# WindRose_V01_0B.net
KiCad netlist of a schematic drawn in EAGLE
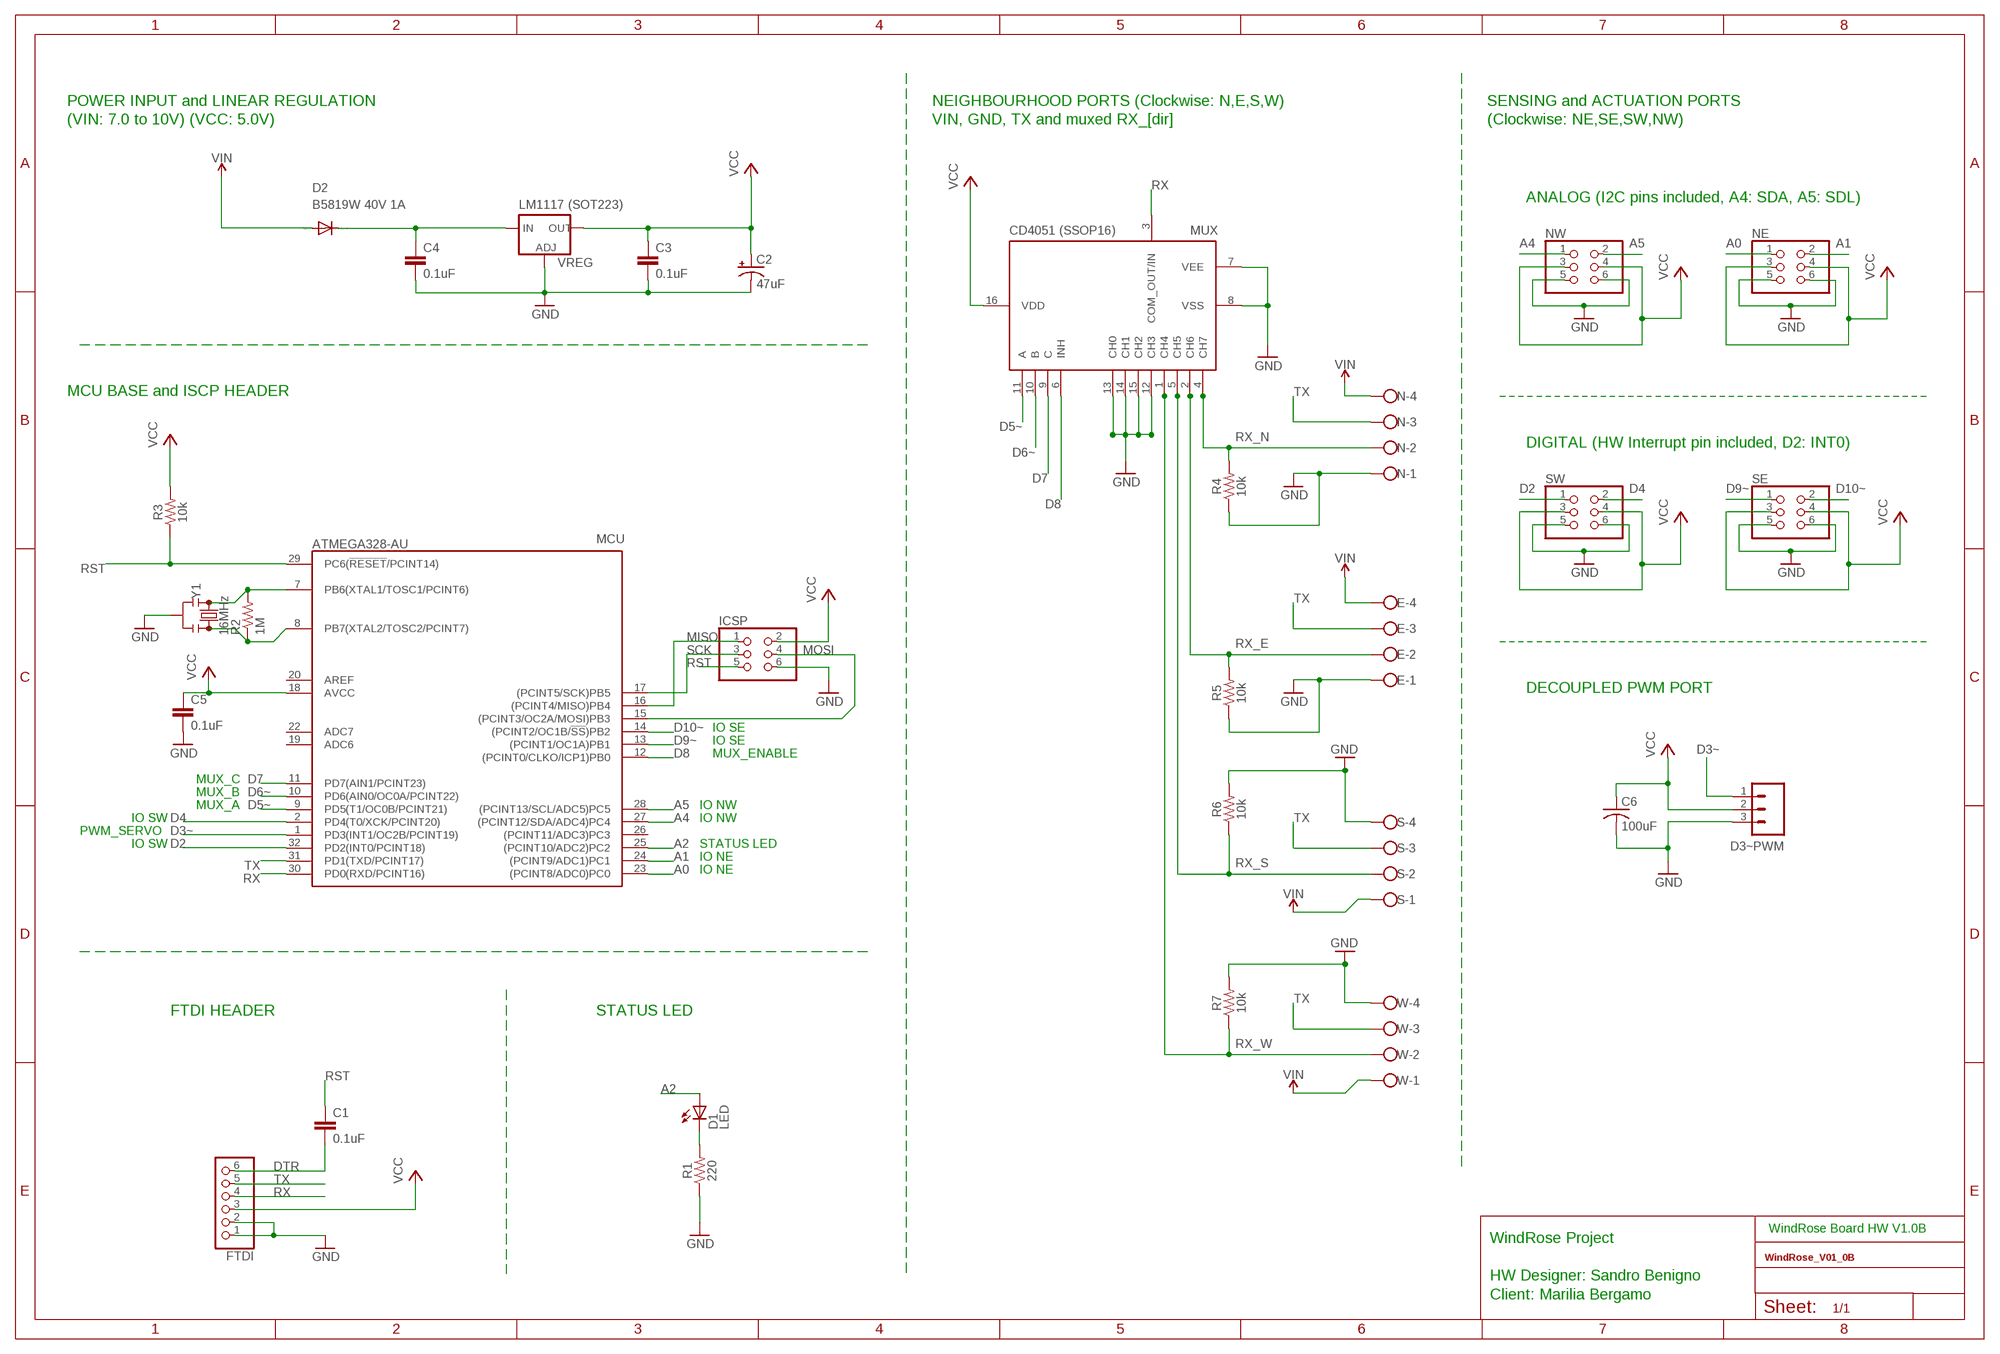
[diagram p0: schematic, sheet 1]

(export (version "E")
  (design (tool "Eeschema 10.0.6"))
  (components
    (comp (ref "C1")
      (value "0.1uF")
      (footprint "eagle-import:0402")
      (libsource (lib "eagle-import") (part "0.1UF-0402-6.3V-10%-X7R"))
    )
    (comp (ref "C2")
      (value "47uF")
      (footprint "eagle-import:EIA3216")
      (libsource (lib "eagle-import") (part "10UF-POLAR-EIA3216-16V-10%(TANT)"))
    )
    (comp (ref "C3")
      (value "0.1uF")
      (footprint "eagle-import:0402")
      (libsource (lib "eagle-import") (part "0.1UF-0402-6.3V-10%-X7R"))
    )
    (comp (ref "C4")
      (value "0.1uF")
      (footprint "eagle-import:0402")
      (libsource (lib "eagle-import") (part "0.1UF-0402-6.3V-10%-X7R"))
    )
    (comp (ref "C5")
      (value "0.1uF")
      (footprint "eagle-import:0402")
      (libsource (lib "eagle-import") (part "0.1UF-0402-6.3V-10%-X7R"))
    )
    (comp (ref "C6")
      (value "100uF")
      (footprint "eagle-import:C3216")
      (libsource (lib "eagle-import") (part "C-USC3216"))
    )
    (comp (ref "D1")
      (value "LED")
      (footprint "eagle-import:CHIP-LED0805")
      (libsource (lib "eagle-import") (part "LEDCHIP-LED0805"))
    )
    (comp (ref "D2")
      (value "B5819W 40V 1A")
      (footprint "eagle-import:SOD123")
      (libsource (lib "eagle-import") (part "DIODE-SOD123"))
    )
    (comp (ref "D3~PWM")
      (value "455-1750-1-ND")
      (footprint "eagle-import:1X03")
      (libsource (lib "eagle-import") (part "CONN_03"))
    )
    (comp (ref "E")
      (value "W237-4")
      (footprint "eagle-import:W237-4")
      (libsource (lib "eagle-import") (part "W237-4"))
    )
    (comp (ref "FTDI")
      (value "PINHD-1X6B")
      (footprint "eagle-import:1X06-BIG")
      (libsource (lib "eagle-import") (part "PINHD-1X6B"))
    )
    (comp (ref "ICSP")
      (value "PINHD-2X3")
      (footprint "eagle-import:2X03")
      (libsource (lib "eagle-import") (part "pinhead_PINHD-2X3"))
    )
    (comp (ref "MCU")
      (value "ATMEGA328-AU")
      (footprint "eagle-import:QFP32_7X7_0.80")
      (libsource (lib "eagle-import") (part "ATMEGA8-AU32"))
    )
    (comp (ref "MUX")
      (value "CD4051SSOP16")
      (footprint "eagle-import:SSOP16")
      (libsource (lib "eagle-import") (part "CD4051SSOP16"))
    )
    (comp (ref "N")
      (value "W237-4")
      (footprint "eagle-import:W237-4")
      (libsource (lib "eagle-import") (part "W237-4"))
    )
    (comp (ref "NE")
      (value "PINHD-2X3")
      (footprint "eagle-import:2X03")
      (libsource (lib "eagle-import") (part "PINHD-2X3"))
    )
    (comp (ref "NW")
      (value "PINHD-2X3")
      (footprint "eagle-import:2X03")
      (libsource (lib "eagle-import") (part "PINHD-2X3"))
    )
    (comp (ref "R1")
      (value "220")
      (footprint "eagle-import:0603")
      (libsource (lib "eagle-import") (part "220OHM-0603-1/10W-1%"))
    )
    (comp (ref "R2")
      (value "1M")
      (footprint "eagle-import:R0402")
      (libsource (lib "eagle-import") (part "R-US_R0402"))
    )
    (comp (ref "R3")
      (value "10k")
      (footprint "eagle-import:0402")
      (libsource (lib "eagle-import") (part "10KOHM-0402-1/16W-1%"))
    )
    (comp (ref "R4")
      (value "10k")
      (footprint "eagle-import:0402")
      (libsource (lib "eagle-import") (part "10KOHM-0402-1/16W-1%"))
    )
    (comp (ref "R5")
      (value "10k")
      (footprint "eagle-import:0402")
      (libsource (lib "eagle-import") (part "10KOHM-0402-1/16W-1%"))
    )
    (comp (ref "R6")
      (value "10k")
      (footprint "eagle-import:0402")
      (libsource (lib "eagle-import") (part "10KOHM-0402-1/16W-1%"))
    )
    (comp (ref "R7")
      (value "10k")
      (footprint "eagle-import:0402")
      (libsource (lib "eagle-import") (part "10KOHM-0402-1/16W-1%"))
    )
    (comp (ref "S")
      (value "W237-4")
      (footprint "eagle-import:W237-4")
      (libsource (lib "eagle-import") (part "W237-4"))
    )
    (comp (ref "SE")
      (value "PINHD-2X3")
      (footprint "eagle-import:2X03")
      (libsource (lib "eagle-import") (part "PINHD-2X3"))
    )
    (comp (ref "SW")
      (value "PINHD-2X3")
      (footprint "eagle-import:2X03")
      (libsource (lib "eagle-import") (part "PINHD-2X3"))
    )
    (comp (ref "VREG")
      (value "V_REG_LM1117SOT223")
      (footprint "eagle-import:SOT223")
      (libsource (lib "eagle-import") (part "V_REG_LM1117SOT223"))
    )
    (comp (ref "W")
      (value "W237-4")
      (footprint "eagle-import:W237-4")
      (libsource (lib "eagle-import") (part "W237-4"))
    )
    (comp (ref "Y1")
      (value "16MHz")
      (footprint "eagle-import:RESONATOR-SMD-3.2X1.3")
      (libsource (lib "eagle-import") (part "RESONATOR-16MHZSMD_3.2X1.3"))
    )
  )
  (nets
    (net (code "1") (name "/A0") (class "Default")
      (node (ref "MCU") (pin "23") (pinfunction "(PCINT8/ADC0)PC0_23") (pintype "bidirectional"))
      (node (ref "NE") (pin "1") (pinfunction "1_1") (pintype "passive"))
    )
    (net (code "2") (name "/A1") (class "Default")
      (node (ref "MCU") (pin "24") (pinfunction "(PCINT9/ADC1)PC1_24") (pintype "bidirectional"))
      (node (ref "NE") (pin "2") (pinfunction "2_2") (pintype "passive"))
    )
    (net (code "3") (name "/A2") (class "Default")
      (node (ref "D1") (pin "A") (pinfunction "A_A") (pintype "passive"))
      (node (ref "MCU") (pin "25") (pinfunction "(PCINT10/ADC2)PC2_25") (pintype "bidirectional"))
    )
    (net (code "4") (name "/A4") (class "Default")
      (node (ref "MCU") (pin "27") (pinfunction "(PCINT12/SDA/ADC4)PC4_27") (pintype "bidirectional"))
      (node (ref "NW") (pin "1") (pinfunction "1_1") (pintype "passive"))
    )
    (net (code "5") (name "/A5") (class "Default")
      (node (ref "MCU") (pin "28") (pinfunction "(PCINT13/SCL/ADC5)PC5_28") (pintype "bidirectional"))
      (node (ref "NW") (pin "2") (pinfunction "2_2") (pintype "passive"))
    )
    (net (code "6") (name "/D2") (class "Default")
      (node (ref "MCU") (pin "32") (pinfunction "PD2(INT0/PCINT18)_32") (pintype "bidirectional"))
      (node (ref "SW") (pin "1") (pinfunction "1_1") (pintype "passive"))
    )
    (net (code "7") (name "/D3~{}") (class "Default")
      (node (ref "D3~PWM") (pin "1") (pinfunction "1_1") (pintype "passive"))
      (node (ref "MCU") (pin "1") (pinfunction "PD3(INT1/OC2B/PCINT19)_1") (pintype "bidirectional"))
    )
    (net (code "8") (name "/D4") (class "Default")
      (node (ref "MCU") (pin "2") (pinfunction "PD4(T0/XCK/PCINT20)_2") (pintype "bidirectional"))
      (node (ref "SW") (pin "2") (pinfunction "2_2") (pintype "passive"))
    )
    (net (code "9") (name "/D5~{}") (class "Default")
      (node (ref "MCU") (pin "9") (pinfunction "PD5(T1/OC0B/PCINT21)_9") (pintype "bidirectional"))
      (node (ref "MUX") (pin "11") (pinfunction "A_11") (pintype "bidirectional"))
    )
    (net (code "10") (name "/D6~{}") (class "Default")
      (node (ref "MCU") (pin "10") (pinfunction "PD6(AIN0/OC0A/PCINT22)_10") (pintype "bidirectional"))
      (node (ref "MUX") (pin "10") (pinfunction "B_10") (pintype "bidirectional"))
    )
    (net (code "11") (name "/D7") (class "Default")
      (node (ref "MCU") (pin "11") (pinfunction "PD7(AIN1/PCINT23)_11") (pintype "bidirectional"))
      (node (ref "MUX") (pin "9") (pinfunction "C_9") (pintype "bidirectional"))
    )
    (net (code "12") (name "/D8") (class "Default")
      (node (ref "MCU") (pin "12") (pinfunction "(PCINT0/CLKO/ICP1)PB0_12") (pintype "bidirectional"))
      (node (ref "MUX") (pin "6") (pinfunction "INH_6") (pintype "bidirectional"))
    )
    (net (code "13") (name "/D9~{}") (class "Default")
      (node (ref "MCU") (pin "13") (pinfunction "(PCINT1/OC1A)PB1_13") (pintype "bidirectional"))
      (node (ref "SE") (pin "1") (pinfunction "1_1") (pintype "passive"))
    )
    (net (code "14") (name "/D10~{}") (class "Default")
      (node (ref "MCU") (pin "14") (pinfunction "(PCINT2/OC1B/~{SS})PB2_14") (pintype "bidirectional"))
      (node (ref "SE") (pin "2") (pinfunction "2_2") (pintype "passive"))
    )
    (net (code "15") (name "/DTR") (class "Default")
      (node (ref "C1") (pin "2") (pinfunction "2_2") (pintype "passive"))
      (node (ref "FTDI") (pin "6") (pinfunction "6_6") (pintype "passive"))
    )
    (net (code "16") (name "/MISO") (class "Default")
      (node (ref "ICSP") (pin "1") (pinfunction "1_1") (pintype "passive"))
      (node (ref "MCU") (pin "16") (pinfunction "(PCINT4/MISO)PB4_16") (pintype "bidirectional"))
    )
    (net (code "17") (name "/MOSI") (class "Default")
      (node (ref "ICSP") (pin "4") (pinfunction "4_4") (pintype "passive"))
      (node (ref "MCU") (pin "15") (pinfunction "(PCINT3/OC2A/MOSI)PB3_15") (pintype "bidirectional"))
    )
    (net (code "19") (name "/RST") (class "Default")
      (node (ref "C1") (pin "1") (pinfunction "1_1") (pintype "passive"))
      (node (ref "ICSP") (pin "5") (pinfunction "5_5") (pintype "passive"))
      (node (ref "MCU") (pin "29") (pinfunction "PC6(~{RESET}/PCINT14)_29") (pintype "bidirectional"))
      (node (ref "R3") (pin "1") (pinfunction "1_1") (pintype "passive"))
    )
    (net (code "20") (name "/RX") (class "Default")
      (node (ref "FTDI") (pin "4") (pinfunction "4_4") (pintype "passive"))
      (node (ref "MCU") (pin "30") (pinfunction "PD0(RXD/PCINT16)_30") (pintype "bidirectional"))
      (node (ref "MUX") (pin "3") (pinfunction "COM_OUT/IN_3") (pintype "bidirectional"))
    )
    (net (code "21") (name "/RX_E") (class "Default")
      (node (ref "E") (pin "2") (pinfunction "KL_2") (pintype "passive"))
      (node (ref "MUX") (pin "2") (pinfunction "CH6_2") (pintype "bidirectional"))
      (node (ref "R5") (pin "2") (pinfunction "2_2") (pintype "passive"))
    )
    (net (code "22") (name "/RX_N") (class "Default")
      (node (ref "MUX") (pin "4") (pinfunction "CH7_4") (pintype "bidirectional"))
      (node (ref "N") (pin "2") (pinfunction "KL_2") (pintype "passive"))
      (node (ref "R4") (pin "2") (pinfunction "2_2") (pintype "passive"))
    )
    (net (code "23") (name "/RX_S") (class "Default")
      (node (ref "MUX") (pin "5") (pinfunction "CH5_5") (pintype "bidirectional"))
      (node (ref "R6") (pin "1") (pinfunction "1_1") (pintype "passive"))
      (node (ref "S") (pin "2") (pinfunction "KL_2") (pintype "passive"))
    )
    (net (code "24") (name "/RX_W") (class "Default")
      (node (ref "MUX") (pin "1") (pinfunction "CH4_1") (pintype "bidirectional"))
      (node (ref "R7") (pin "1") (pinfunction "1_1") (pintype "passive"))
      (node (ref "W") (pin "2") (pinfunction "KL_2") (pintype "passive"))
    )
    (net (code "25") (name "/SCK") (class "Default")
      (node (ref "ICSP") (pin "3") (pinfunction "3_3") (pintype "passive"))
      (node (ref "MCU") (pin "17") (pinfunction "(PCINT5/SCK)PB5_17") (pintype "bidirectional"))
    )
    (net (code "26") (name "/TX") (class "Default")
      (node (ref "E") (pin "3") (pinfunction "KL_3") (pintype "passive"))
      (node (ref "FTDI") (pin "5") (pinfunction "5_5") (pintype "passive"))
      (node (ref "MCU") (pin "31") (pinfunction "PD1(TXD/PCINT17)_31") (pintype "bidirectional"))
      (node (ref "N") (pin "3") (pinfunction "KL_3") (pintype "passive"))
      (node (ref "S") (pin "3") (pinfunction "KL_3") (pintype "passive"))
      (node (ref "W") (pin "3") (pinfunction "KL_3") (pintype "passive"))
    )
    (net (code "27") (name "GND") (class "Default")
      (node (ref "C2") (pin "-") (pinfunction "-_-") (pintype "passive"))
      (node (ref "C3") (pin "2") (pinfunction "2_2") (pintype "passive"))
      (node (ref "C4") (pin "2") (pinfunction "2_2") (pintype "passive"))
      (node (ref "C5") (pin "2") (pinfunction "2_2") (pintype "passive"))
      (node (ref "C6") (pin "2") (pinfunction "2_2") (pintype "passive"))
      (node (ref "D3~PWM") (pin "3") (pinfunction "3_3") (pintype "passive"))
      (node (ref "E") (pin "1") (pinfunction "KL_1") (pintype "passive"))
      (node (ref "FTDI") (pin "1") (pinfunction "1_1") (pintype "passive"))
      (node (ref "FTDI") (pin "2") (pinfunction "2_2") (pintype "passive"))
      (node (ref "ICSP") (pin "6") (pinfunction "6_6") (pintype "passive"))
      (node (ref "MUX") (pin "12") (pinfunction "CH3_12") (pintype "bidirectional"))
      (node (ref "MUX") (pin "13") (pinfunction "CH0_13") (pintype "bidirectional"))
      (node (ref "MUX") (pin "14") (pinfunction "CH1_14") (pintype "bidirectional"))
      (node (ref "MUX") (pin "15") (pinfunction "CH2_15") (pintype "bidirectional"))
      (node (ref "MUX") (pin "7") (pinfunction "VEE_7") (pintype "bidirectional"))
      (node (ref "MUX") (pin "8") (pinfunction "VSS_8") (pintype "bidirectional"))
      (node (ref "N") (pin "1") (pinfunction "KL_1") (pintype "passive"))
      (node (ref "NE") (pin "5") (pinfunction "5_5") (pintype "passive"))
      (node (ref "NE") (pin "6") (pinfunction "6_6") (pintype "passive"))
      (node (ref "NW") (pin "5") (pinfunction "5_5") (pintype "passive"))
      (node (ref "NW") (pin "6") (pinfunction "6_6") (pintype "passive"))
      (node (ref "R1") (pin "1") (pinfunction "1_1") (pintype "passive"))
      (node (ref "R4") (pin "1") (pinfunction "1_1") (pintype "passive"))
      (node (ref "R5") (pin "1") (pinfunction "1_1") (pintype "passive"))
      (node (ref "R6") (pin "2") (pinfunction "2_2") (pintype "passive"))
      (node (ref "R7") (pin "2") (pinfunction "2_2") (pintype "passive"))
      (node (ref "S") (pin "4") (pinfunction "KL_4") (pintype "passive"))
      (node (ref "SE") (pin "5") (pinfunction "5_5") (pintype "passive"))
      (node (ref "SE") (pin "6") (pinfunction "6_6") (pintype "passive"))
      (node (ref "SW") (pin "5") (pinfunction "5_5") (pintype "passive"))
      (node (ref "SW") (pin "6") (pinfunction "6_6") (pintype "passive"))
      (node (ref "VREG") (pin "1") (pinfunction "ADJ_1") (pintype "input"))
      (node (ref "W") (pin "4") (pinfunction "KL_4") (pintype "passive"))
      (node (ref "Y1") (pin "2") (pinfunction "2_2") (pintype "passive"))
    )
    (net (code "28") (name "Net-(D1-PadC)") (class "Default")
      (node (ref "D1") (pin "C") (pinfunction "C_C") (pintype "passive"))
      (node (ref "R1") (pin "2") (pinfunction "2_2") (pintype "passive"))
    )
    (net (code "29") (name "Net-(MCUA-PB6(XTAL1{slash}TOSC1{slash}PCINT6))") (class "Default")
      (node (ref "MCU") (pin "7") (pinfunction "PB6(XTAL1/TOSC1/PCINT6)_7") (pintype "bidirectional"))
      (node (ref "R2") (pin "2") (pinfunction "2_2") (pintype "passive"))
      (node (ref "Y1") (pin "1") (pinfunction "1_1") (pintype "passive"))
    )
    (net (code "30") (name "Net-(MCUA-PB7(XTAL2{slash}TOSC2{slash}PCINT7))") (class "Default")
      (node (ref "MCU") (pin "8") (pinfunction "PB7(XTAL2/TOSC2/PCINT7)_8") (pintype "bidirectional"))
      (node (ref "R2") (pin "1") (pinfunction "1_1") (pintype "passive"))
      (node (ref "Y1") (pin "3") (pinfunction "3_3") (pintype "passive"))
    )
    (net (code "31") (name "Net-(VREG-IN)") (class "Default")
      (node (ref "C4") (pin "1") (pinfunction "1_1") (pintype "passive"))
      (node (ref "D2") (pin "C") (pinfunction "C_C") (pintype "passive"))
      (node (ref "VREG") (pin "3") (pinfunction "IN_3") (pintype "input"))
    )
    (net (code "32") (name "VCC") (class "Default")
      (node (ref "C2") (pin "+") (pinfunction "+_+") (pintype "passive"))
      (node (ref "C3") (pin "1") (pinfunction "1_1") (pintype "passive"))
      (node (ref "C5") (pin "1") (pinfunction "1_1") (pintype "passive"))
      (node (ref "C6") (pin "1") (pinfunction "1_1") (pintype "passive"))
      (node (ref "D3~PWM") (pin "2") (pinfunction "2_2") (pintype "passive"))
      (node (ref "FTDI") (pin "3") (pinfunction "3_3") (pintype "passive"))
      (node (ref "ICSP") (pin "2") (pinfunction "2_2") (pintype "passive"))
      (node (ref "MCU") (pin "18") (pinfunction "AVCC_18") (pintype "power_in"))
      (node (ref "MUX") (pin "16") (pinfunction "VDD_16") (pintype "bidirectional"))
      (node (ref "NE") (pin "3") (pinfunction "3_3") (pintype "passive"))
      (node (ref "NE") (pin "4") (pinfunction "4_4") (pintype "passive"))
      (node (ref "NW") (pin "3") (pinfunction "3_3") (pintype "passive"))
      (node (ref "NW") (pin "4") (pinfunction "4_4") (pintype "passive"))
      (node (ref "R3") (pin "2") (pinfunction "2_2") (pintype "passive"))
      (node (ref "SE") (pin "3") (pinfunction "3_3") (pintype "passive"))
      (node (ref "SE") (pin "4") (pinfunction "4_4") (pintype "passive"))
      (node (ref "SW") (pin "3") (pinfunction "3_3") (pintype "passive"))
      (node (ref "SW") (pin "4") (pinfunction "4_4") (pintype "passive"))
      (node (ref "VREG") (pin "2") (pinfunction "OUT_2") (pintype "output"))
      (node (ref "VREG") (pin "4") (pinfunction "OUT_4") (pintype "output"))
    )
    (net (code "33") (name "VIN") (class "Default")
      (node (ref "D2") (pin "A") (pinfunction "A_A") (pintype "passive"))
      (node (ref "E") (pin "4") (pinfunction "KL_4") (pintype "passive"))
      (node (ref "N") (pin "4") (pinfunction "KL_4") (pintype "passive"))
      (node (ref "S") (pin "1") (pinfunction "KL_1") (pintype "passive"))
      (node (ref "W") (pin "1") (pinfunction "KL_1") (pintype "passive"))
    )
    (net (code "34") (name "unconnected-(MCUA-(PCINT11{slash}ADC3)PC3-Pad26)") (class "Default")
      (node (ref "MCU") (pin "26") (pinfunction "(PCINT11/ADC3)PC3_26") (pintype "bidirectional"))
    )
    (net (code "35") (name "unconnected-(MCUA-ADC6-Pad19)") (class "Default")
      (node (ref "MCU") (pin "19") (pinfunction "ADC6_19") (pintype "bidirectional"))
    )
    (net (code "36") (name "unconnected-(MCUA-ADC7-Pad22)") (class "Default")
      (node (ref "MCU") (pin "22") (pinfunction "ADC7_22") (pintype "bidirectional"))
    )
    (net (code "37") (name "unconnected-(MCUA-AREF-Pad20)") (class "Default")
      (node (ref "MCU") (pin "20") (pinfunction "AREF_20") (pintype "passive"))
    )
  )
)
